# main.net
KiCad netlist of a schematic drawn in EAGLE
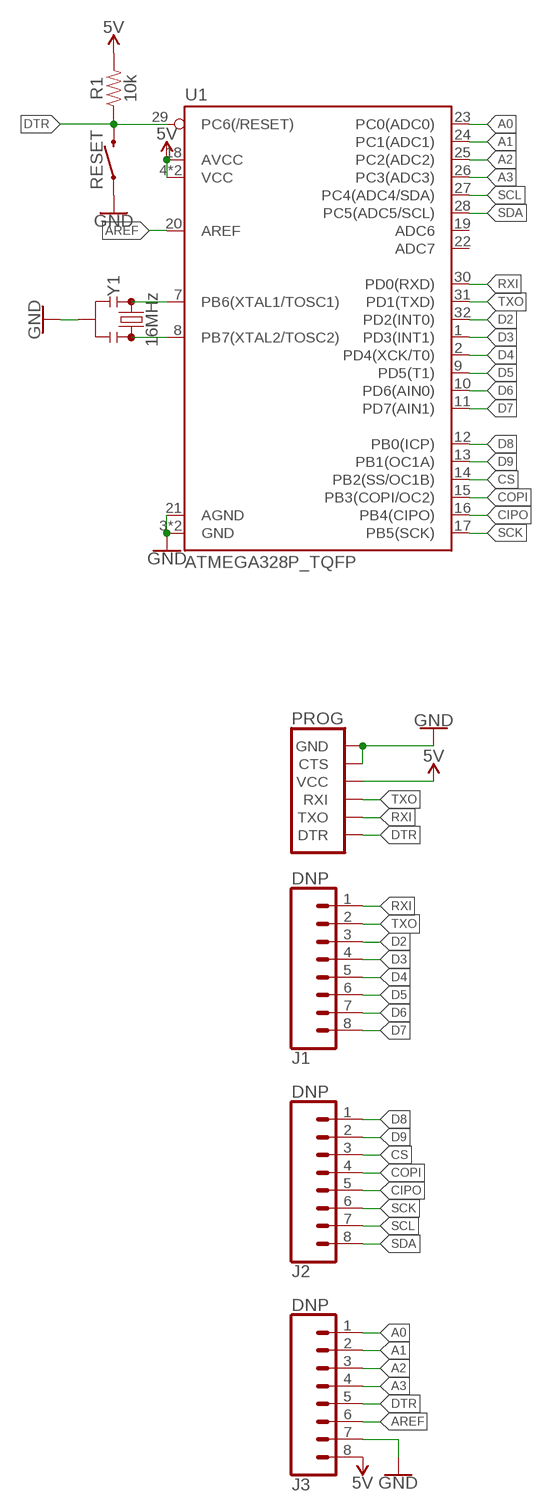
[diagram p0: schematic, sheet 1]

(export (version "E")
  (design (tool "Eeschema 10.0.6"))
  (components
    (comp (ref "J1")
      (value "DNP")
      (footprint "eagle-import:1X08")
      (libsource (lib "eagle-import") (part "CONN_08{dblquote}"))
    )
    (comp (ref "J2")
      (value "DNP")
      (footprint "eagle-import:1X08")
      (libsource (lib "eagle-import") (part "CONN_08{dblquote}"))
    )
    (comp (ref "J3")
      (value "DNP")
      (footprint "eagle-import:1X08")
      (libsource (lib "eagle-import") (part "CONN_08{dblquote}"))
    )
    (comp (ref "PROG")
      (value "6_PIN_SERIAL_TARGETSILK")
      (footprint "eagle-import:6_PIN_SERIAL_TARGET_SIDE_W_SILK")
      (libsource (lib "eagle-import") (part "6_PIN_SERIAL_TARGETSILK"))
    )
    (comp (ref "R1")
      (value "10k")
      (footprint "eagle-import:0402")
      (libsource (lib "eagle-import") (part "10KOHM-0402-1/16W-1%"))
    )
    (comp (ref "RESET")
      (value "MOMENTARY-SWITCH-SPST-SMD-6.0X3.5MM")
      (footprint "eagle-import:TACTILE_SWITCH_SMD_6.0X3.5MM")
      (libsource (lib "eagle-import") (part "MOMENTARY-SWITCH-SPST-SMD-6.0X3.5MM"))
    )
    (comp (ref "U1")
      (value "ATMEGA328P_TQFP")
      (footprint "eagle-import:TQFP32-08")
      (libsource (lib "eagle-import") (part "ATMEGA328P_TQFP"))
    )
    (comp (ref "Y1")
      (value "16MHz")
      (footprint "eagle-import:RESONATOR-SMD-3.2X1.3")
      (libsource (lib "eagle-import") (part "RESONATOR-16MHZSMD_3.2X1.3"))
    )
  )
  (nets
    (net (code "1") (name "5V") (class "Default")
      (node (ref "J3") (pin "8") (pinfunction "8_8") (pintype "passive"))
      (node (ref "PROG") (pin "4") (pinfunction "VCC_4") (pintype "passive"))
      (node (ref "R1") (pin "2") (pinfunction "2_2") (pintype "passive"))
      (node (ref "U1") (pin "18") (pinfunction "AVCC_18") (pintype "bidirectional"))
      (node (ref "U1") (pin "4") (pinfunction "VCC_4") (pintype "bidirectional"))
      (node (ref "U1") (pin "6") (pinfunction "VCC_6") (pintype "bidirectional"))
    )
    (net (code "2") (name "A0") (class "Default")
      (node (ref "J3") (pin "1") (pinfunction "1_1") (pintype "passive"))
      (node (ref "U1") (pin "23") (pinfunction "PC0(ADC0)_23") (pintype "bidirectional"))
    )
    (net (code "3") (name "A1") (class "Default")
      (node (ref "J3") (pin "2") (pinfunction "2_2") (pintype "passive"))
      (node (ref "U1") (pin "24") (pinfunction "PC1(ADC1)_24") (pintype "bidirectional"))
    )
    (net (code "4") (name "A2") (class "Default")
      (node (ref "J3") (pin "3") (pinfunction "3_3") (pintype "passive"))
      (node (ref "U1") (pin "25") (pinfunction "PC2(ADC2)_25") (pintype "bidirectional"))
    )
    (net (code "5") (name "A3") (class "Default")
      (node (ref "J3") (pin "4") (pinfunction "4_4") (pintype "passive"))
      (node (ref "U1") (pin "26") (pinfunction "PC3(ADC3)_26") (pintype "bidirectional"))
    )
    (net (code "6") (name "AREF") (class "Default")
      (node (ref "J3") (pin "6") (pinfunction "6_6") (pintype "passive"))
      (node (ref "U1") (pin "20") (pinfunction "AREF_20") (pintype "bidirectional"))
    )
    (net (code "7") (name "CIPO") (class "Default")
      (node (ref "J2") (pin "5") (pinfunction "5_5") (pintype "passive"))
      (node (ref "U1") (pin "16") (pinfunction "PB4(CIPO)_16") (pintype "bidirectional"))
    )
    (net (code "8") (name "COPI") (class "Default")
      (node (ref "J2") (pin "4") (pinfunction "4_4") (pintype "passive"))
      (node (ref "U1") (pin "15") (pinfunction "PB3(COPI/OC2)_15") (pintype "bidirectional"))
    )
    (net (code "9") (name "CS") (class "Default")
      (node (ref "J2") (pin "3") (pinfunction "3_3") (pintype "passive"))
      (node (ref "U1") (pin "14") (pinfunction "PB2(SS/OC1B)_14") (pintype "bidirectional"))
    )
    (net (code "10") (name "D2") (class "Default")
      (node (ref "J1") (pin "3") (pinfunction "3_3") (pintype "passive"))
      (node (ref "U1") (pin "32") (pinfunction "PD2(INT0)_32") (pintype "bidirectional"))
    )
    (net (code "11") (name "D3") (class "Default")
      (node (ref "J1") (pin "4") (pinfunction "4_4") (pintype "passive"))
      (node (ref "U1") (pin "1") (pinfunction "PD3(INT1)_1") (pintype "bidirectional"))
    )
    (net (code "12") (name "D4") (class "Default")
      (node (ref "J1") (pin "5") (pinfunction "5_5") (pintype "passive"))
      (node (ref "U1") (pin "2") (pinfunction "PD4(XCK/T0)_2") (pintype "bidirectional"))
    )
    (net (code "13") (name "D5") (class "Default")
      (node (ref "J1") (pin "6") (pinfunction "6_6") (pintype "passive"))
      (node (ref "U1") (pin "9") (pinfunction "PD5(T1)_9") (pintype "bidirectional"))
    )
    (net (code "14") (name "D6") (class "Default")
      (node (ref "J1") (pin "7") (pinfunction "7_7") (pintype "passive"))
      (node (ref "U1") (pin "10") (pinfunction "PD6(AIN0)_10") (pintype "bidirectional"))
    )
    (net (code "15") (name "D7") (class "Default")
      (node (ref "J1") (pin "8") (pinfunction "8_8") (pintype "passive"))
      (node (ref "U1") (pin "11") (pinfunction "PD7(AIN1)_11") (pintype "bidirectional"))
    )
    (net (code "16") (name "D8") (class "Default")
      (node (ref "J2") (pin "1") (pinfunction "1_1") (pintype "passive"))
      (node (ref "U1") (pin "12") (pinfunction "PB0(ICP)_12") (pintype "bidirectional"))
    )
    (net (code "17") (name "D9") (class "Default")
      (node (ref "J2") (pin "2") (pinfunction "2_2") (pintype "passive"))
      (node (ref "U1") (pin "13") (pinfunction "PB1(OC1A)_13") (pintype "bidirectional"))
    )
    (net (code "18") (name "DTR") (class "Default")
      (node (ref "J3") (pin "5") (pinfunction "5_5") (pintype "passive"))
      (node (ref "PROG") (pin "1") (pinfunction "DTR_1") (pintype "passive"))
      (node (ref "R1") (pin "1") (pinfunction "1_1") (pintype "passive"))
      (node (ref "RESET") (pin "2") (pinfunction "2_2") (pintype "passive"))
      (node (ref "U1") (pin "29") (pinfunction "PC6(/RESET)_29") (pintype "bidirectional"))
    )
    (net (code "19") (name "GND") (class "Default")
      (node (ref "J3") (pin "7") (pinfunction "7_7") (pintype "passive"))
      (node (ref "PROG") (pin "5") (pinfunction "CTS_5") (pintype "passive"))
      (node (ref "PROG") (pin "6") (pinfunction "GND_6") (pintype "passive"))
      (node (ref "RESET") (pin "1") (pinfunction "1_1") (pintype "passive"))
      (node (ref "U1") (pin "21") (pinfunction "AGND_21") (pintype "bidirectional"))
      (node (ref "U1") (pin "3") (pinfunction "GND_3") (pintype "bidirectional"))
      (node (ref "U1") (pin "5") (pinfunction "GND_5") (pintype "bidirectional"))
      (node (ref "Y1") (pin "2") (pinfunction "2_2") (pintype "passive"))
    )
    (net (code "20") (name "Net-(U1-PB6(XTAL1{slash}TOSC1))") (class "Default")
      (node (ref "U1") (pin "7") (pinfunction "PB6(XTAL1/TOSC1)_7") (pintype "bidirectional"))
      (node (ref "Y1") (pin "1") (pinfunction "1_1") (pintype "passive"))
    )
    (net (code "21") (name "Net-(U1-PB7(XTAL2{slash}TOSC2))") (class "Default")
      (node (ref "U1") (pin "8") (pinfunction "PB7(XTAL2/TOSC2)_8") (pintype "bidirectional"))
      (node (ref "Y1") (pin "3") (pinfunction "3_3") (pintype "passive"))
    )
    (net (code "22") (name "RXI") (class "Default")
      (node (ref "J1") (pin "1") (pinfunction "1_1") (pintype "passive"))
      (node (ref "PROG") (pin "2") (pinfunction "TXO_2") (pintype "passive"))
      (node (ref "U1") (pin "30") (pinfunction "PD0(RXD)_30") (pintype "bidirectional"))
    )
    (net (code "23") (name "SCK") (class "Default")
      (node (ref "J2") (pin "6") (pinfunction "6_6") (pintype "passive"))
      (node (ref "U1") (pin "17") (pinfunction "PB5(SCK)_17") (pintype "bidirectional"))
    )
    (net (code "24") (name "SCL") (class "Default")
      (node (ref "J2") (pin "7") (pinfunction "7_7") (pintype "passive"))
      (node (ref "U1") (pin "27") (pinfunction "PC4(ADC4/SDA)_27") (pintype "bidirectional"))
    )
    (net (code "25") (name "SDA") (class "Default")
      (node (ref "J2") (pin "8") (pinfunction "8_8") (pintype "passive"))
      (node (ref "U1") (pin "28") (pinfunction "PC5(ADC5/SCL)_28") (pintype "bidirectional"))
    )
    (net (code "26") (name "TXO") (class "Default")
      (node (ref "J1") (pin "2") (pinfunction "2_2") (pintype "passive"))
      (node (ref "PROG") (pin "3") (pinfunction "RXI_3") (pintype "passive"))
      (node (ref "U1") (pin "31") (pinfunction "PD1(TXD)_31") (pintype "bidirectional"))
    )
    (net (code "27") (name "unconnected-(U1-ADC6-Pad19)") (class "Default")
      (node (ref "U1") (pin "19") (pinfunction "ADC6_19") (pintype "bidirectional"))
    )
    (net (code "28") (name "unconnected-(U1-ADC7-Pad22)") (class "Default")
      (node (ref "U1") (pin "22") (pinfunction "ADC7_22") (pintype "bidirectional"))
    )
  )
)
